# balancer.net
KiCad netlist of a schematic drawn in Altium Designer
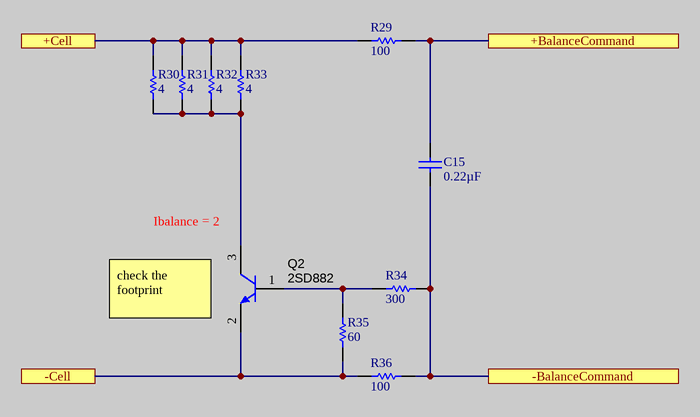
[diagram p0: balancer.SchDoc]

(export (version "E")
  (design (tool "Eeschema 10.0.6"))
  (components
    (comp (ref "C15")
      (value "0.22µF")
      (footprint "CAPC0603")
      (description "Capacitor")
      (fields (field (name "PUBLISHER") "Altium Limited"))
      (libsource (lib "eLIB") (part "Capacitor"))
    )
    (comp (ref "Q2")
      (value "2SD882")
      (footprint "dpak")
      (description "BJT 30V 3A 40V 10W SI-NPN")
      (fields
        (field (name "PARTNUMBER") "BSR14")
        (field (name "MANUFACTURER") "Nexperia")
        (field (name "PUBLISHER") "Texas Instruments")
      )
      (libsource (lib "Bipolar_Transistor") (part "BSR14, Nexperia"))
    )
    (comp (ref "R29")
      (value "100")
      (footprint "RESC0603")
      (description "0603,0.1W")
      (fields (field (name "PUBLISHER") "Altium Limited"))
      (libsource (lib "eLIB") (part "Resistor"))
    )
    (comp (ref "R30")
      (value "4")
      (footprint "RES2512")
      (description "0603,0.1W")
      (fields (field (name "PUBLISHER") "Altium Limited"))
      (libsource (lib "eLIB") (part "Resistor"))
    )
    (comp (ref "R31")
      (value "4")
      (footprint "RES2512")
      (description "0603,0.1W")
      (fields (field (name "PUBLISHER") "Altium Limited"))
      (libsource (lib "eLIB") (part "Resistor"))
    )
    (comp (ref "R32")
      (value "4")
      (footprint "RES2512")
      (description "0603,0.1W")
      (fields (field (name "PUBLISHER") "Altium Limited"))
      (libsource (lib "eLIB") (part "Resistor"))
    )
    (comp (ref "R33")
      (value "4")
      (footprint "RES2512")
      (description "0603,0.1W")
      (fields (field (name "PUBLISHER") "Altium Limited"))
      (libsource (lib "eLIB") (part "Resistor"))
    )
    (comp (ref "R34")
      (value "300")
      (footprint "RESC0603")
      (description "0603,0.1W")
      (fields (field (name "PUBLISHER") "Altium Limited"))
      (libsource (lib "eLIB") (part "Resistor"))
    )
    (comp (ref "R35")
      (value "60")
      (footprint "RESC0603")
      (description "0603,0.1W")
      (fields (field (name "PUBLISHER") "Altium Limited"))
      (libsource (lib "eLIB") (part "Resistor"))
    )
    (comp (ref "R36")
      (value "100")
      (footprint "RESC0603")
      (description "0603,0.1W")
      (fields (field (name "PUBLISHER") "Altium Limited"))
      (libsource (lib "eLIB") (part "Resistor"))
    )
  )
  (nets
    (net (code "1") (name "/+BalanceCommand") (class "Default")
      (node (ref "C15") (pin "2") (pinfunction "2_2") (pintype "passive"))
      (node (ref "R29") (pin "2") (pinfunction "2_2") (pintype "passive"))
    )
    (net (code "2") (name "/+Cell") (class "Default")
      (node (ref "R29") (pin "1") (pinfunction "1_1") (pintype "passive"))
      (node (ref "R30") (pin "1") (pinfunction "1_1") (pintype "passive"))
      (node (ref "R31") (pin "1") (pinfunction "1_1") (pintype "passive"))
      (node (ref "R32") (pin "1") (pinfunction "1_1") (pintype "passive"))
      (node (ref "R33") (pin "1") (pinfunction "1_1") (pintype "passive"))
    )
    (net (code "3") (name "/-BalanceCommand") (class "Default")
      (node (ref "C15") (pin "1") (pinfunction "1_1") (pintype "passive"))
      (node (ref "R34") (pin "2") (pinfunction "2_2") (pintype "passive"))
      (node (ref "R36") (pin "2") (pinfunction "2_2") (pintype "passive"))
    )
    (net (code "4") (name "/-Cell") (class "Default")
      (node (ref "Q2") (pin "2") (pinfunction "E_2") (pintype "passive"))
      (node (ref "R35") (pin "1") (pinfunction "1_1") (pintype "passive"))
      (node (ref "R36") (pin "1") (pinfunction "1_1") (pintype "passive"))
    )
    (net (code "5") (name "Net-(Q2-B)") (class "Default")
      (node (ref "Q2") (pin "1") (pinfunction "B_1") (pintype "passive"))
      (node (ref "R34") (pin "1") (pinfunction "1_1") (pintype "passive"))
      (node (ref "R35") (pin "2") (pinfunction "2_2") (pintype "passive"))
    )
    (net (code "6") (name "Net-(Q2-C)") (class "Default")
      (node (ref "Q2") (pin "3") (pinfunction "C_3") (pintype "passive"))
      (node (ref "R30") (pin "2") (pinfunction "2_2") (pintype "passive"))
      (node (ref "R31") (pin "2") (pinfunction "2_2") (pintype "passive"))
      (node (ref "R32") (pin "2") (pinfunction "2_2") (pintype "passive"))
      (node (ref "R33") (pin "2") (pinfunction "2_2") (pintype "passive"))
    )
  )
)
